# Audio-DAC-D.net
KiCad netlist of a schematic drawn in EAGLE
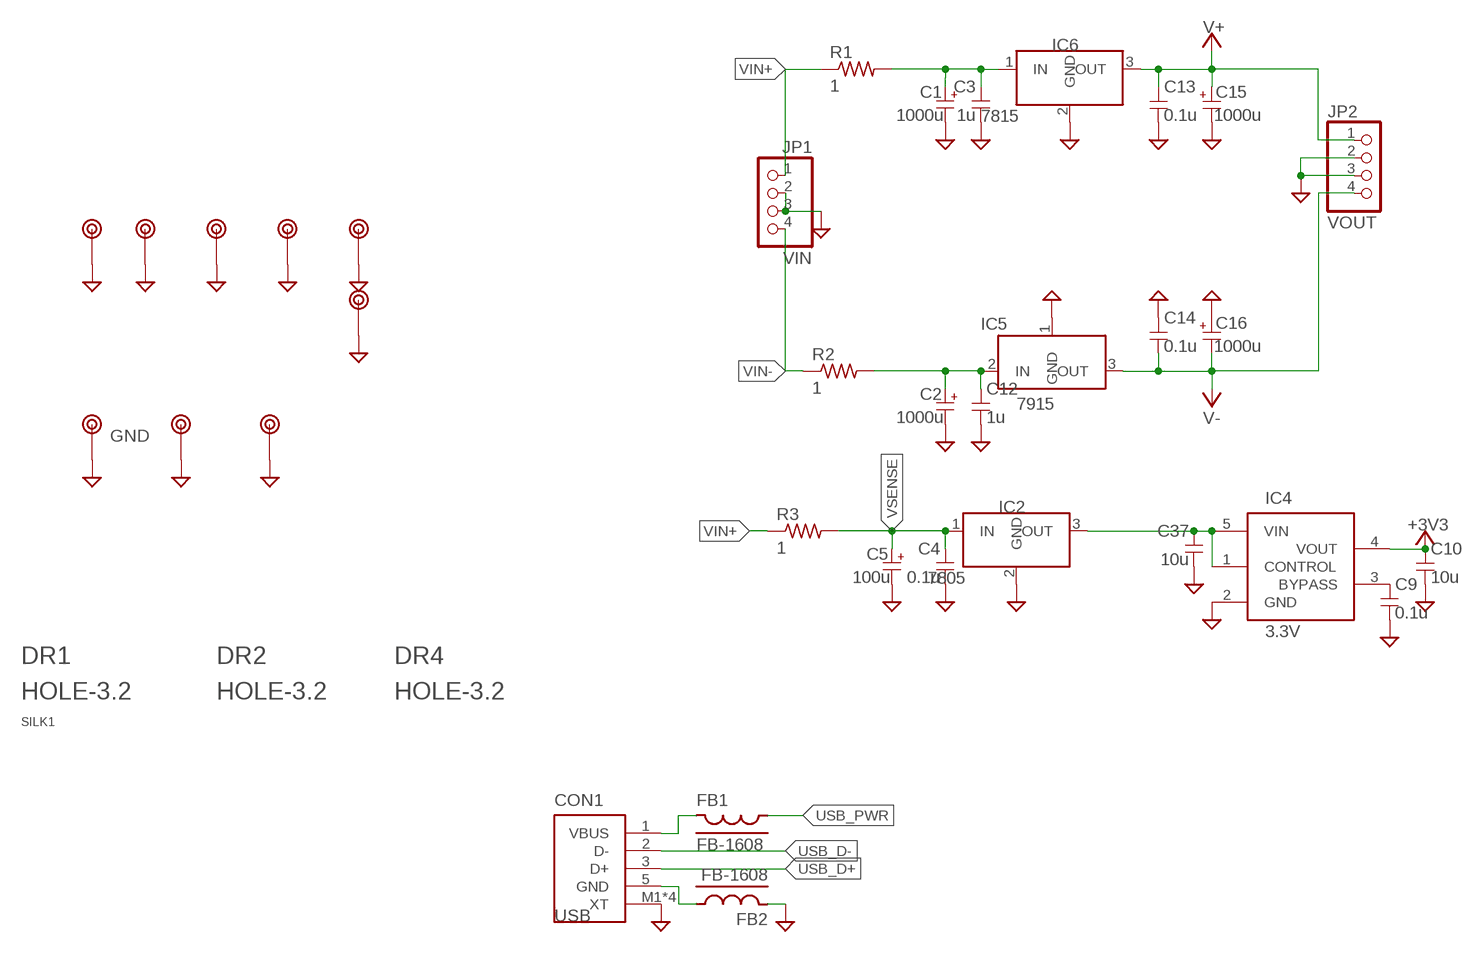
[diagram p0: schematic, sheet 1, part 1 of 2]
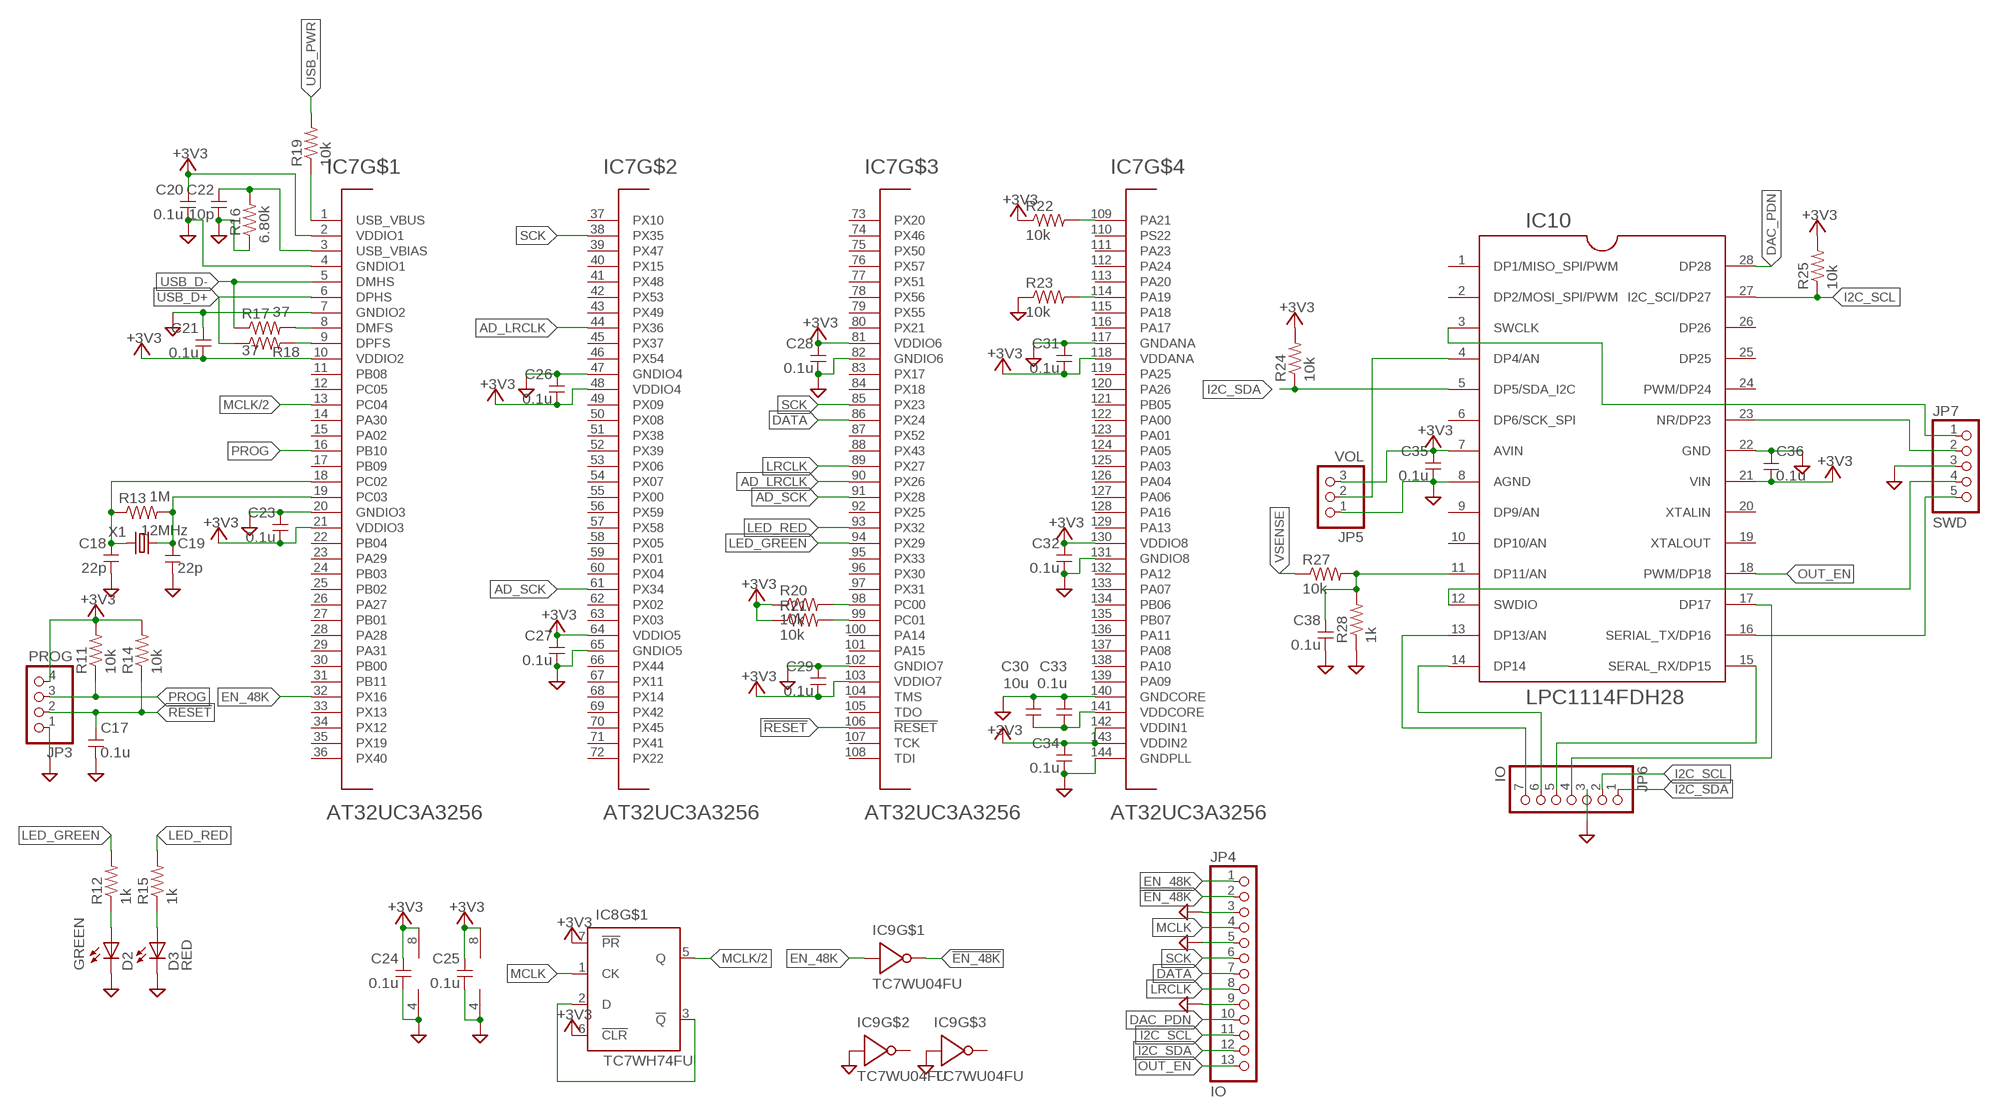
[diagram p1: schematic, sheet 1, part 2 of 2]

(export (version "E")
  (design (tool "Eeschema 10.0.6"))
  (components
    (comp (ref "C1")
      (value "1000u")
      (footprint "eagle-import:E5-10")
      (libsource (lib "eagle-import") (part "CPOLE5-10"))
    )
    (comp (ref "C2")
      (value "1000u")
      (footprint "eagle-import:E5-10")
      (libsource (lib "eagle-import") (part "CPOLE5-10"))
    )
    (comp (ref "C3")
      (value "1u")
      (footprint "eagle-import:1608")
      (libsource (lib "eagle-import") (part "C-1608"))
    )
    (comp (ref "C4")
      (value "0.1u")
      (footprint "eagle-import:1608")
      (libsource (lib "eagle-import") (part "C-1608"))
    )
    (comp (ref "C5")
      (value "100u")
      (footprint "eagle-import:E2.5-6.5")
      (libsource (lib "eagle-import") (part "CPOLE2.5-6.5"))
    )
    (comp (ref "C9")
      (value "0.1u")
      (footprint "eagle-import:1608")
      (libsource (lib "eagle-import") (part "C-1608"))
    )
    (comp (ref "C10")
      (value "10u")
      (footprint "eagle-import:2012")
      (libsource (lib "eagle-import") (part "C-2012"))
    )
    (comp (ref "C12")
      (value "1u")
      (footprint "eagle-import:1608")
      (libsource (lib "eagle-import") (part "C-1608"))
    )
    (comp (ref "C13")
      (value "0.1u")
      (footprint "eagle-import:2012")
      (libsource (lib "eagle-import") (part "C-2012"))
    )
    (comp (ref "C14")
      (value "0.1u")
      (footprint "eagle-import:2012")
      (libsource (lib "eagle-import") (part "C-2012"))
    )
    (comp (ref "C15")
      (value "1000u")
      (footprint "eagle-import:E5-10")
      (libsource (lib "eagle-import") (part "CPOLE5-10"))
    )
    (comp (ref "C16")
      (value "1000u")
      (footprint "eagle-import:E5-10")
      (libsource (lib "eagle-import") (part "CPOLE5-10"))
    )
    (comp (ref "C17")
      (value "0.1u")
      (footprint "eagle-import:1608")
      (libsource (lib "eagle-import") (part "C-1608"))
    )
    (comp (ref "C18")
      (value "22p")
      (footprint "eagle-import:1608")
      (libsource (lib "eagle-import") (part "C-1608"))
    )
    (comp (ref "C19")
      (value "22p")
      (footprint "eagle-import:1608")
      (libsource (lib "eagle-import") (part "C-1608"))
    )
    (comp (ref "C20")
      (value "0.1u")
      (footprint "eagle-import:1608")
      (libsource (lib "eagle-import") (part "C-1608"))
    )
    (comp (ref "C21")
      (value "0.1u")
      (footprint "eagle-import:1608")
      (libsource (lib "eagle-import") (part "C-1608"))
    )
    (comp (ref "C22")
      (value "10p")
      (footprint "eagle-import:1608")
      (libsource (lib "eagle-import") (part "C-1608"))
    )
    (comp (ref "C23")
      (value "0.1u")
      (footprint "eagle-import:1608")
      (libsource (lib "eagle-import") (part "C-1608"))
    )
    (comp (ref "C24")
      (value "0.1u")
      (footprint "eagle-import:1608")
      (libsource (lib "eagle-import") (part "C-1608"))
    )
    (comp (ref "C25")
      (value "0.1u")
      (footprint "eagle-import:1608")
      (libsource (lib "eagle-import") (part "C-1608"))
    )
    (comp (ref "C26")
      (value "0.1u")
      (footprint "eagle-import:1608")
      (libsource (lib "eagle-import") (part "C-1608"))
    )
    (comp (ref "C27")
      (value "0.1u")
      (footprint "eagle-import:1608")
      (libsource (lib "eagle-import") (part "C-1608"))
    )
    (comp (ref "C28")
      (value "0.1u")
      (footprint "eagle-import:1608")
      (libsource (lib "eagle-import") (part "C-1608"))
    )
    (comp (ref "C29")
      (value "0.1u")
      (footprint "eagle-import:1608")
      (libsource (lib "eagle-import") (part "C-1608"))
    )
    (comp (ref "C30")
      (value "10u")
      (footprint "eagle-import:2012")
      (libsource (lib "eagle-import") (part "C-2012"))
    )
    (comp (ref "C31")
      (value "0.1u")
      (footprint "eagle-import:1608")
      (libsource (lib "eagle-import") (part "C-1608"))
    )
    (comp (ref "C32")
      (value "0.1u")
      (footprint "eagle-import:1608")
      (libsource (lib "eagle-import") (part "C-1608"))
    )
    (comp (ref "C33")
      (value "0.1u")
      (footprint "eagle-import:1608")
      (libsource (lib "eagle-import") (part "C-1608"))
    )
    (comp (ref "C34")
      (value "0.1u")
      (footprint "eagle-import:1608")
      (libsource (lib "eagle-import") (part "C-1608"))
    )
    (comp (ref "C35")
      (value "0.1u")
      (footprint "eagle-import:1608")
      (libsource (lib "eagle-import") (part "C-1608"))
    )
    (comp (ref "C36")
      (value "0.1u")
      (footprint "eagle-import:1608")
      (libsource (lib "eagle-import") (part "C-1608"))
    )
    (comp (ref "C37")
      (value "10u")
      (footprint "eagle-import:2012")
      (libsource (lib "eagle-import") (part "C-2012"))
    )
    (comp (ref "C38")
      (value "0.1u")
      (footprint "eagle-import:1608")
      (libsource (lib "eagle-import") (part "C-1608"))
    )
    (comp (ref "CON1")
      (value "USB")
      (footprint "eagle-import:UX60A-MB-5ST")
      (libsource (lib "eagle-import") (part "USB"))
    )
    (comp (ref "D2")
      (value "GREEN")
      (footprint "eagle-import:D1608")
      (libsource (lib "eagle-import") (part "LED-SMD1608"))
    )
    (comp (ref "D3")
      (value "RED")
      (footprint "eagle-import:D1608")
      (libsource (lib "eagle-import") (part "LED-SMD1608"))
    )
    (comp (ref "DR1")
      (value "HOLE-3.2")
      (footprint "eagle-import:HOLE_3.2")
      (libsource (lib "eagle-import") (part "HOLE-3.2"))
    )
    (comp (ref "DR2")
      (value "HOLE-3.2")
      (footprint "eagle-import:HOLE_3.2")
      (libsource (lib "eagle-import") (part "HOLE-3.2"))
    )
    (comp (ref "DR4")
      (value "HOLE-3.2")
      (footprint "eagle-import:HOLE_3.2")
      (libsource (lib "eagle-import") (part "HOLE-3.2"))
    )
    (comp (ref "FB1")
      (value "FB-1608")
      (footprint "eagle-import:1608")
      (libsource (lib "eagle-import") (part "FB-1608"))
    )
    (comp (ref "FB2")
      (value "FB-1608")
      (footprint "eagle-import:1608")
      (libsource (lib "eagle-import") (part "FB-1608"))
    )
    (comp (ref "IC2")
      (value "7805")
      (footprint "eagle-import:7805-LARGEHOLE")
      (libsource (lib "eagle-import") (part "78X-1"))
    )
    (comp (ref "IC4")
      (value "3.3V")
      (footprint "eagle-import:SOT23-5")
      (libsource (lib "eagle-import") (part "NJM2863"))
    )
    (comp (ref "IC5")
      (value "7915")
      (footprint "eagle-import:7805-LARGEHOLE")
      (libsource (lib "eagle-import") (part "79X-1"))
    )
    (comp (ref "IC6")
      (value "7815")
      (footprint "eagle-import:7805-LARGEHOLE")
      (libsource (lib "eagle-import") (part "78X-1"))
    )
    (comp (ref "IC7")
      (value "AT32UC3A3256")
      (footprint "eagle-import:TQFP144")
      (libsource (lib "eagle-import") (part "AT32UC3A3256"))
    )
    (comp (ref "IC8")
      (value "TC7WH74FU")
      (footprint "eagle-import:SSOP8-P-0.65")
      (libsource (lib "eagle-import") (part "TC7WH74FU"))
    )
    (comp (ref "IC9")
      (value "TC7WU04FU")
      (footprint "eagle-import:SSOP8-P-0.65")
      (libsource (lib "eagle-import") (part "TC7WU04FU"))
    )
    (comp (ref "IC10")
      (value "LPC1114FDH28")
      (footprint "eagle-import:TSSOP28")
      (libsource (lib "eagle-import") (part "LPC1114FDH28"))
    )
    (comp (ref "JP1")
      (value "VIN")
      (footprint "eagle-import:1X04")
      (libsource (lib "eagle-import") (part "PINHD-1X4"))
    )
    (comp (ref "JP2")
      (value "VOUT")
      (footprint "eagle-import:1X04")
      (libsource (lib "eagle-import") (part "PINHD-1X4"))
    )
    (comp (ref "JP3")
      (value "PROG")
      (footprint "eagle-import:1X04")
      (libsource (lib "eagle-import") (part "PINHD-1X4"))
    )
    (comp (ref "JP4")
      (value "IO")
      (footprint "eagle-import:1X13")
      (libsource (lib "eagle-import") (part "PINHD-1X13"))
    )
    (comp (ref "JP5")
      (value "VOL")
      (footprint "eagle-import:1X03")
      (libsource (lib "eagle-import") (part "PINHD-1X3"))
    )
    (comp (ref "JP6")
      (value "IO")
      (footprint "eagle-import:1X07")
      (libsource (lib "eagle-import") (part "PINHD-1X7"))
    )
    (comp (ref "JP7")
      (value "SWD")
      (footprint "eagle-import:1X05")
      (libsource (lib "eagle-import") (part "PINHD-1X5"))
    )
    (comp (ref "R1")
      (value "1")
      (footprint "eagle-import:0204_7")
      (libsource (lib "eagle-import") (part "R-7.5"))
    )
    (comp (ref "R2")
      (value "1")
      (footprint "eagle-import:0204_7")
      (libsource (lib "eagle-import") (part "R-7.5"))
    )
    (comp (ref "R3")
      (value "1")
      (footprint "eagle-import:0204_7")
      (libsource (lib "eagle-import") (part "R-7.5"))
    )
    (comp (ref "R11")
      (value "10k")
      (footprint "eagle-import:1608")
      (libsource (lib "eagle-import") (part "R-1608"))
    )
    (comp (ref "R12")
      (value "1k")
      (footprint "eagle-import:1608")
      (libsource (lib "eagle-import") (part "R-1608"))
    )
    (comp (ref "R13")
      (value "1M")
      (footprint "eagle-import:0204_7")
      (libsource (lib "eagle-import") (part "R-7.5"))
    )
    (comp (ref "R14")
      (value "10k")
      (footprint "eagle-import:1608")
      (libsource (lib "eagle-import") (part "R-1608"))
    )
    (comp (ref "R15")
      (value "1k")
      (footprint "eagle-import:1608")
      (libsource (lib "eagle-import") (part "R-1608"))
    )
    (comp (ref "R16")
      (value "6.80k")
      (footprint "eagle-import:1608")
      (libsource (lib "eagle-import") (part "R-1608"))
    )
    (comp (ref "R17")
      (value "37")
      (footprint "eagle-import:1608")
      (libsource (lib "eagle-import") (part "R-1608"))
    )
    (comp (ref "R18")
      (value "37")
      (footprint "eagle-import:1608")
      (libsource (lib "eagle-import") (part "R-1608"))
    )
    (comp (ref "R19")
      (value "10k")
      (footprint "eagle-import:1608")
      (libsource (lib "eagle-import") (part "R-1608"))
    )
    (comp (ref "R20")
      (value "10k")
      (footprint "eagle-import:1608")
      (libsource (lib "eagle-import") (part "R-1608"))
    )
    (comp (ref "R21")
      (value "10k")
      (footprint "eagle-import:1608")
      (libsource (lib "eagle-import") (part "R-1608"))
    )
    (comp (ref "R22")
      (value "10k")
      (footprint "eagle-import:1608")
      (libsource (lib "eagle-import") (part "R-1608"))
    )
    (comp (ref "R23")
      (value "10k")
      (footprint "eagle-import:1608")
      (libsource (lib "eagle-import") (part "R-1608"))
    )
    (comp (ref "R24")
      (value "10k")
      (footprint "eagle-import:1608")
      (libsource (lib "eagle-import") (part "R-1608"))
    )
    (comp (ref "R25")
      (value "10k")
      (footprint "eagle-import:1608")
      (libsource (lib "eagle-import") (part "R-1608"))
    )
    (comp (ref "R27")
      (value "10k")
      (footprint "eagle-import:1608")
      (libsource (lib "eagle-import") (part "R-1608"))
    )
    (comp (ref "R28")
      (value "1k")
      (footprint "eagle-import:1608")
      (libsource (lib "eagle-import") (part "R-1608"))
    )
    (comp (ref "SILK1")
      (value "ROBOTECHWHEELSILK-9MM")
      (footprint "eagle-import:ROBOTECHWHEEL-9MM")
      (libsource (lib "eagle-import") (part "ROBOTECHWHEELSILK-9MM"))
    )
    (comp (ref "TP1")
      (value "TESTPIN")
      (footprint "eagle-import:TESTPIN")
      (libsource (lib "eagle-import") (part "TESTPIN"))
    )
    (comp (ref "TP2")
      (value "GND")
      (footprint "eagle-import:TESTPIN")
      (libsource (lib "eagle-import") (part "TESTPIN"))
    )
    (comp (ref "TP3")
      (value "TESTPIN")
      (footprint "eagle-import:TESTPIN")
      (libsource (lib "eagle-import") (part "TESTPIN"))
    )
    (comp (ref "TP4")
      (value "TESTPIN")
      (footprint "eagle-import:TESTPIN")
      (libsource (lib "eagle-import") (part "TESTPIN"))
    )
    (comp (ref "TP5")
      (value "TESTPIN")
      (footprint "eagle-import:TESTPIN")
      (libsource (lib "eagle-import") (part "TESTPIN"))
    )
    (comp (ref "TP6")
      (value "TESTPIN")
      (footprint "eagle-import:TESTPIN")
      (libsource (lib "eagle-import") (part "TESTPIN"))
    )
    (comp (ref "TP7")
      (value "TESTPIN")
      (footprint "eagle-import:TESTPIN")
      (libsource (lib "eagle-import") (part "TESTPIN"))
    )
    (comp (ref "TP8")
      (value "TESTPIN")
      (footprint "eagle-import:TESTPIN")
      (libsource (lib "eagle-import") (part "TESTPIN"))
    )
    (comp (ref "TP9")
      (value "TESTPIN")
      (footprint "eagle-import:TESTPIN")
      (libsource (lib "eagle-import") (part "TESTPIN"))
    )
    (comp (ref "X1")
      (value "12MHz")
      (footprint "eagle-import:HC49_S")
      (libsource (lib "eagle-import") (part "CRYSTALHC49S"))
    )
  )
  (nets
    (net (code "1") (name "+3V3") (class "Default")
      (node (ref "C10") (pin "1") (pinfunction "1_1") (pintype "passive"))
      (node (ref "C20") (pin "1") (pinfunction "1_1") (pintype "passive"))
      (node (ref "C21") (pin "2") (pinfunction "2_2") (pintype "passive"))
      (node (ref "C23") (pin "2") (pinfunction "2_2") (pintype "passive"))
      (node (ref "C24") (pin "1") (pinfunction "1_1") (pintype "passive"))
      (node (ref "C25") (pin "1") (pinfunction "1_1") (pintype "passive"))
      (node (ref "C26") (pin "2") (pinfunction "2_2") (pintype "passive"))
      (node (ref "C27") (pin "1") (pinfunction "1_1") (pintype "passive"))
      (node (ref "C28") (pin "1") (pinfunction "1_1") (pintype "passive"))
      (node (ref "C29") (pin "2") (pinfunction "2_2") (pintype "passive"))
      (node (ref "C31") (pin "2") (pinfunction "2_2") (pintype "passive"))
      (node (ref "C32") (pin "1") (pinfunction "1_1") (pintype "passive"))
      (node (ref "C34") (pin "1") (pinfunction "1_1") (pintype "passive"))
      (node (ref "C35") (pin "1") (pinfunction "1_1") (pintype "passive"))
      (node (ref "C36") (pin "2") (pinfunction "2_2") (pintype "passive"))
      (node (ref "IC10") (pin "21") (pinfunction "VIN_21") (pintype "power_in"))
      (node (ref "IC10") (pin "7") (pinfunction "AVIN_7") (pintype "power_in"))
      (node (ref "IC4") (pin "4") (pinfunction "VOUT_4") (pintype "power_in"))
      (node (ref "IC7") (pin "10") (pinfunction "VDDIO2_10") (pintype "power_in"))
      (node (ref "IC7") (pin "103") (pinfunction "VDDIO7_103") (pintype "power_in"))
      (node (ref "IC7") (pin "118") (pinfunction "VDDANA_118") (pintype "power_in"))
      (node (ref "IC7") (pin "130") (pinfunction "VDDIO8_130") (pintype "power_in"))
      (node (ref "IC7") (pin "142") (pinfunction "VDDIN1_142") (pintype "power_in"))
      (node (ref "IC7") (pin "143") (pinfunction "VDDIN2_143") (pintype "power_in"))
      (node (ref "IC7") (pin "2") (pinfunction "VDDIO1_2") (pintype "power_in"))
      (node (ref "IC7") (pin "21") (pinfunction "VDDIO3_21") (pintype "power_in"))
      (node (ref "IC7") (pin "48") (pinfunction "VDDIO4_48") (pintype "power_in"))
      (node (ref "IC7") (pin "64") (pinfunction "VDDIO5_64") (pintype "power_in"))
      (node (ref "IC7") (pin "81") (pinfunction "VDDIO6_81") (pintype "power_in"))
      (node (ref "IC8") (pin "6") (pinfunction "~{CLR}_6") (pintype "input"))
      (node (ref "IC8") (pin "7") (pinfunction "~{PR}_7") (pintype "input"))
      (node (ref "IC8") (pin "8") (pinfunction "V+_8") (pintype "power_in"))
      (node (ref "IC9") (pin "8") (pinfunction "V+_8") (pintype "power_in"))
      (node (ref "JP3") (pin "4") (pinfunction "4_4") (pintype "passive"))
      (node (ref "JP5") (pin "3") (pinfunction "3_3") (pintype "passive"))
      (node (ref "R11") (pin "2") (pinfunction "2_2") (pintype "passive"))
      (node (ref "R14") (pin "2") (pinfunction "2_2") (pintype "passive"))
      (node (ref "R20") (pin "1") (pinfunction "1_1") (pintype "passive"))
      (node (ref "R21") (pin "1") (pinfunction "1_1") (pintype "passive"))
      (node (ref "R22") (pin "1") (pinfunction "1_1") (pintype "passive"))
      (node (ref "R24") (pin "2") (pinfunction "2_2") (pintype "passive"))
      (node (ref "R25") (pin "2") (pinfunction "2_2") (pintype "passive"))
    )
    (net (code "2") (name "/~{EN_48K}") (class "Default")
      (node (ref "IC9") (pin "7") (pinfunction "P$2_7") (pintype "output"))
      (node (ref "JP4") (pin "2") (pinfunction "2_2") (pintype "passive"))
    )
    (net (code "3") (name "/~{RESET}") (class "Default")
      (node (ref "C17") (pin "1") (pinfunction "1_1") (pintype "passive"))
      (node (ref "IC7") (pin "106") (pinfunction "~{RESET}_106") (pintype "input"))
      (node (ref "JP3") (pin "2") (pinfunction "2_2") (pintype "passive"))
      (node (ref "R14") (pin "1") (pinfunction "1_1") (pintype "passive"))
    )
    (net (code "4") (name "AD_LRCLK") (class "Default")
      (node (ref "IC7") (pin "44") (pinfunction "PX36_44") (pintype "bidirectional"))
      (node (ref "IC7") (pin "90") (pinfunction "PX26_90") (pintype "bidirectional"))
    )
    (net (code "5") (name "AD_SCK") (class "Default")
      (node (ref "IC7") (pin "61") (pinfunction "PX34_61") (pintype "bidirectional"))
      (node (ref "IC7") (pin "91") (pinfunction "PX28_91") (pintype "bidirectional"))
    )
    (net (code "6") (name "DAC_PDN") (class "Default")
      (node (ref "IC10") (pin "28") (pinfunction "DP28_28") (pintype "bidirectional"))
      (node (ref "JP4") (pin "10") (pinfunction "10_10") (pintype "passive"))
    )
    (net (code "7") (name "DATA") (class "Default")
      (node (ref "IC7") (pin "86") (pinfunction "PX24_86") (pintype "bidirectional"))
      (node (ref "JP4") (pin "7") (pinfunction "7_7") (pintype "passive"))
    )
    (net (code "8") (name "EN_48K") (class "Default")
      (node (ref "IC7") (pin "32") (pinfunction "PX16_32") (pintype "bidirectional"))
      (node (ref "IC9") (pin "1") (pinfunction "P$1_1") (pintype "input"))
      (node (ref "JP4") (pin "1") (pinfunction "1_1") (pintype "passive"))
    )
    (net (code "9") (name "GND") (class "Default")
      (node (ref "C1") (pin "-") (pinfunction "2_-") (pintype "passive"))
      (node (ref "C10") (pin "2") (pinfunction "2_2") (pintype "passive"))
      (node (ref "C12") (pin "2") (pinfunction "2_2") (pintype "passive"))
      (node (ref "C13") (pin "2") (pinfunction "2_2") (pintype "passive"))
      (node (ref "C14") (pin "1") (pinfunction "1_1") (pintype "passive"))
      (node (ref "C15") (pin "-") (pinfunction "2_-") (pintype "passive"))
      (node (ref "C16") (pin "+") (pinfunction "1_+") (pintype "passive"))
      (node (ref "C17") (pin "2") (pinfunction "2_2") (pintype "passive"))
      (node (ref "C18") (pin "2") (pinfunction "2_2") (pintype "passive"))
      (node (ref "C19") (pin "2") (pinfunction "2_2") (pintype "passive"))
      (node (ref "C2") (pin "-") (pinfunction "2_-") (pintype "passive"))
      (node (ref "C20") (pin "2") (pinfunction "2_2") (pintype "passive"))
      (node (ref "C21") (pin "1") (pinfunction "1_1") (pintype "passive"))
      (node (ref "C22") (pin "2") (pinfunction "2_2") (pintype "passive"))
      (node (ref "C23") (pin "1") (pinfunction "1_1") (pintype "passive"))
      (node (ref "C24") (pin "2") (pinfunction "2_2") (pintype "passive"))
      (node (ref "C25") (pin "2") (pinfunction "2_2") (pintype "passive"))
      (node (ref "C26") (pin "1") (pinfunction "1_1") (pintype "passive"))
      (node (ref "C27") (pin "2") (pinfunction "2_2") (pintype "passive"))
      (node (ref "C28") (pin "2") (pinfunction "2_2") (pintype "passive"))
      (node (ref "C29") (pin "1") (pinfunction "1_1") (pintype "passive"))
      (node (ref "C3") (pin "2") (pinfunction "2_2") (pintype "passive"))
      (node (ref "C30") (pin "1") (pinfunction "1_1") (pintype "passive"))
      (node (ref "C31") (pin "1") (pinfunction "1_1") (pintype "passive"))
      (node (ref "C32") (pin "2") (pinfunction "2_2") (pintype "passive"))
      (node (ref "C33") (pin "1") (pinfunction "1_1") (pintype "passive"))
      (node (ref "C34") (pin "2") (pinfunction "2_2") (pintype "passive"))
      (node (ref "C35") (pin "2") (pinfunction "2_2") (pintype "passive"))
      (node (ref "C36") (pin "1") (pinfunction "1_1") (pintype "passive"))
      (node (ref "C37") (pin "2") (pinfunction "2_2") (pintype "passive"))
      (node (ref "C38") (pin "2") (pinfunction "2_2") (pintype "passive"))
      (node (ref "C4") (pin "2") (pinfunction "2_2") (pintype "passive"))
      (node (ref "C5") (pin "-") (pinfunction "2_-") (pintype "passive"))
      (node (ref "C9") (pin "2") (pinfunction "2_2") (pintype "passive"))
      (node (ref "CON1") (pin "M1") (pinfunction "XT_M1") (pintype "power_in"))
      (node (ref "CON1") (pin "M2") (pinfunction "XT_M2") (pintype "power_in"))
      (node (ref "CON1") (pin "M3") (pinfunction "XT_M3") (pintype "power_in"))
      (node (ref "CON1") (pin "M4") (pinfunction "XT_M4") (pintype "power_in"))
      (node (ref "D2") (pin "K") (pinfunction "K_K") (pintype "passive"))
      (node (ref "D3") (pin "K") (pinfunction "K_K") (pintype "passive"))
      (node (ref "FB2") (pin "2") (pinfunction "2_2") (pintype "passive"))
      (node (ref "IC10") (pin "22") (pinfunction "GND_22") (pintype "power_in"))
      (node (ref "IC10") (pin "8") (pinfunction "AGND_8") (pintype "power_in"))
      (node (ref "IC2") (pin "2") (pinfunction "GND_2") (pintype "power_in"))
      (node (ref "IC4") (pin "2") (pinfunction "GND_2") (pintype "power_in"))
      (node (ref "IC5") (pin "1") (pinfunction "GND_1") (pintype "input"))
      (node (ref "IC6") (pin "2") (pinfunction "GND_2") (pintype "power_in"))
      (node (ref "IC7") (pin "102") (pinfunction "GNDIO7_102") (pintype "power_in"))
      (node (ref "IC7") (pin "117") (pinfunction "GNDANA_117") (pintype "power_in"))
      (node (ref "IC7") (pin "131") (pinfunction "GNDIO8_131") (pintype "power_in"))
      (node (ref "IC7") (pin "140") (pinfunction "GNDCORE_140") (pintype "power_in"))
      (node (ref "IC7") (pin "144") (pinfunction "GNDPLL_144") (pintype "power_in"))
      (node (ref "IC7") (pin "20") (pinfunction "GNDIO3_20") (pintype "power_in"))
      (node (ref "IC7") (pin "4") (pinfunction "GNDIO1_4") (pintype "power_in"))
      (node (ref "IC7") (pin "47") (pinfunction "GNDIO4_47") (pintype "power_in"))
      (node (ref "IC7") (pin "65") (pinfunction "GNDIO5_65") (pintype "power_in"))
      (node (ref "IC7") (pin "7") (pinfunction "GNDIO2_7") (pintype "power_in"))
      (node (ref "IC7") (pin "82") (pinfunction "GNDIO6_82") (pintype "power_in"))
      (node (ref "IC8") (pin "4") (pinfunction "V-_4") (pintype "power_in"))
      (node (ref "IC9") (pin "3") (pinfunction "P$1_3") (pintype "input"))
      (node (ref "IC9") (pin "4") (pinfunction "V-_4") (pintype "power_in"))
      (node (ref "IC9") (pin "6") (pinfunction "P$1_6") (pintype "input"))
      (node (ref "JP1") (pin "2") (pinfunction "2_2") (pintype "passive"))
      (node (ref "JP1") (pin "3") (pinfunction "3_3") (pintype "passive"))
      (node (ref "JP2") (pin "2") (pinfunction "2_2") (pintype "passive"))
      (node (ref "JP2") (pin "3") (pinfunction "3_3") (pintype "passive"))
      (node (ref "JP3") (pin "1") (pinfunction "1_1") (pintype "passive"))
      (node (ref "JP4") (pin "3") (pinfunction "3_3") (pintype "passive"))
      (node (ref "JP4") (pin "5") (pinfunction "5_5") (pintype "passive"))
      (node (ref "JP4") (pin "9") (pinfunction "9_9") (pintype "passive"))
      (node (ref "JP5") (pin "1") (pinfunction "1_1") (pintype "passive"))
      (node (ref "JP6") (pin "3") (pinfunction "3_3") (pintype "passive"))
      (node (ref "JP7") (pin "3") (pinfunction "3_3") (pintype "passive"))
      (node (ref "R16") (pin "1") (pinfunction "1_1") (pintype "passive"))
      (node (ref "R23") (pin "1") (pinfunction "1_1") (pintype "passive"))
      (node (ref "R28") (pin "1") (pinfunction "1_1") (pintype "passive"))
      (node (ref "TP1") (pin "1") (pinfunction "1_1") (pintype "passive"))
      (node (ref "TP2") (pin "1") (pinfunction "1_1") (pintype "passive"))
      (node (ref "TP3") (pin "1") (pinfunction "1_1") (pintype "passive"))
      (node (ref "TP4") (pin "1") (pinfunction "1_1") (pintype "passive"))
      (node (ref "TP5") (pin "1") (pinfunction "1_1") (pintype "passive"))
      (node (ref "TP6") (pin "1") (pinfunction "1_1") (pintype "passive"))
      (node (ref "TP7") (pin "1") (pinfunction "1_1") (pintype "passive"))
      (node (ref "TP8") (pin "1") (pinfunction "1_1") (pintype "passive"))
      (node (ref "TP9") (pin "1") (pinfunction "1_1") (pintype "passive"))
    )
    (net (code "10") (name "I2C_SCL") (class "Default")
      (node (ref "IC10") (pin "27") (pinfunction "I2C_SCI/DP27_27") (pintype "bidirectional"))
      (node (ref "JP4") (pin "11") (pinfunction "11_11") (pintype "passive"))
      (node (ref "JP6") (pin "2") (pinfunction "2_2") (pintype "passive"))
      (node (ref "R25") (pin "1") (pinfunction "1_1") (pintype "passive"))
    )
    (net (code "11") (name "I2C_SDA") (class "Default")
      (node (ref "IC10") (pin "5") (pinfunction "DP5/SDA_I2C_5") (pintype "bidirectional"))
      (node (ref "JP4") (pin "12") (pinfunction "12_12") (pintype "passive"))
      (node (ref "JP6") (pin "1") (pinfunction "1_1") (pintype "passive"))
      (node (ref "R24") (pin "1") (pinfunction "1_1") (pintype "passive"))
    )
    (net (code "12") (name "LED_GREEN") (class "Default")
      (node (ref "IC7") (pin "94") (pinfunction "PX29_94") (pintype "bidirectional"))
      (node (ref "R12") (pin "2") (pinfunction "2_2") (pintype "passive"))
    )
    (net (code "13") (name "LED_RED") (class "Default")
      (node (ref "IC7") (pin "93") (pinfunction "PX32_93") (pintype "bidirectional"))
      (node (ref "R15") (pin "2") (pinfunction "2_2") (pintype "passive"))
    )
    (net (code "14") (name "LRCLK") (class "Default")
      (node (ref "IC7") (pin "89") (pinfunction "PX27_89") (pintype "bidirectional"))
      (node (ref "JP4") (pin "8") (pinfunction "8_8") (pintype "passive"))
    )
    (net (code "15") (name "MCLK") (class "Default")
      (node (ref "IC8") (pin "1") (pinfunction "CK_1") (pintype "input"))
      (node (ref "JP4") (pin "4") (pinfunction "4_4") (pintype "passive"))
    )
    (net (code "16") (name "MCLK{slash}2") (class "Default")
      (node (ref "IC7") (pin "13") (pinfunction "PC04_13") (pintype "bidirectional"))
      (node (ref "IC8") (pin "5") (pinfunction "Q_5") (pintype "output"))
    )
    (net (code "17") (name "Net-(C1-1)") (class "Default")
      (node (ref "C1") (pin "+") (pinfunction "1_+") (pintype "passive"))
      (node (ref "C3") (pin "1") (pinfunction "1_1") (pintype "passive"))
      (node (ref "IC6") (pin "1") (pinfunction "IN_1") (pintype "power_in"))
      (node (ref "R1") (pin "2") (pinfunction "2_2") (pintype "passive"))
    )
    (net (code "18") (name "Net-(C2-1)") (class "Default")
      (node (ref "C12") (pin "1") (pinfunction "1_1") (pintype "passive"))
      (node (ref "C2") (pin "+") (pinfunction "1_+") (pintype "passive"))
      (node (ref "IC5") (pin "2") (pinfunction "IN_2") (pintype "input"))
      (node (ref "R2") (pin "2") (pinfunction "2_2") (pintype "passive"))
    )
    (net (code "19") (name "Net-(CON1-GND)") (class "Default")
      (node (ref "CON1") (pin "5") (pinfunction "GND_5") (pintype "power_in"))
      (node (ref "FB2") (pin "1") (pinfunction "1_1") (pintype "passive"))
    )
    (net (code "20") (name "Net-(CON1-VBUS)") (class "Default")
      (node (ref "CON1") (pin "1") (pinfunction "VBUS_1") (pintype "power_in"))
      (node (ref "FB1") (pin "2") (pinfunction "2_2") (pintype "passive"))
    )
    (net (code "21") (name "Net-(D2-PadA)") (class "Default")
      (node (ref "D2") (pin "A") (pinfunction "A_A") (pintype "passive"))
      (node (ref "R12") (pin "1") (pinfunction "1_1") (pintype "passive"))
    )
    (net (code "22") (name "Net-(D3-PadA)") (class "Default")
      (node (ref "D3") (pin "A") (pinfunction "A_A") (pintype "passive"))
      (node (ref "R15") (pin "1") (pinfunction "1_1") (pintype "passive"))
    )
    (net (code "23") (name "Net-(IC2-OUT)") (class "Default")
      (node (ref "C37") (pin "1") (pinfunction "1_1") (pintype "passive"))
      (node (ref "IC2") (pin "3") (pinfunction "OUT_3") (pintype "output"))
      (node (ref "IC4") (pin "1") (pinfunction "CONTROL_1") (pintype "input"))
      (node (ref "IC4") (pin "5") (pinfunction "VIN_5") (pintype "power_in"))
    )
    (net (code "24") (name "Net-(IC4-BYPASS)") (class "Default")
      (node (ref "C9") (pin "1") (pinfunction "1_1") (pintype "passive"))
      (node (ref "IC4") (pin "3") (pinfunction "BYPASS_3") (pintype "passive"))
    )
    (net (code "25") (name "Net-(IC7A-DMFS)") (class "Default")
      (node (ref "IC7") (pin "8") (pinfunction "DMFS_8") (pintype "bidirectional"))
      (node (ref "R17") (pin "2") (pinfunction "2_2") (pintype "passive"))
    )
    (net (code "26") (name "Net-(IC7A-DPFS)") (class "Default")
      (node (ref "IC7") (pin "9") (pinfunction "DPFS_9") (pintype "bidirectional"))
      (node (ref "R18") (pin "2") (pinfunction "2_2") (pintype "passive"))
    )
    (net (code "27") (name "Net-(IC7A-PC02)") (class "Default")
      (node (ref "C18") (pin "1") (pinfunction "1_1") (pintype "passive"))
      (node (ref "IC7") (pin "18") (pinfunction "PC02_18") (pintype "bidirectional"))
      (node (ref "R13") (pin "1") (pinfunction "1_1") (pintype "passive"))
      (node (ref "X1") (pin "2") (pinfunction "2_2") (pintype "passive"))
    )
    (net (code "28") (name "Net-(IC7A-PC03)") (class "Default")
      (node (ref "C19") (pin "1") (pinfunction "1_1") (pintype "passive"))
      (node (ref "IC7") (pin "19") (pinfunction "PC03_19") (pintype "bidirectional"))
      (node (ref "R13") (pin "2") (pinfunction "2_2") (pintype "passive"))
      (node (ref "X1") (pin "1") (pinfunction "1_1") (pintype "passive"))
    )
    (net (code "29") (name "Net-(IC7A-USB_VBIAS)") (class "Default")
      (node (ref "C22") (pin "1") (pinfunction "1_1") (pintype "passive"))
      (node (ref "IC7") (pin "3") (pinfunction "USB_VBIAS_3") (pintype "input"))
      (node (ref "R16") (pin "2") (pinfunction "2_2") (pintype "passive"))
    )
    (net (code "30") (name "Net-(IC7A-USB_VBUS)") (class "Default")
      (node (ref "IC7") (pin "1") (pinfunction "USB_VBUS_1") (pintype "input"))
      (node (ref "R19") (pin "1") (pinfunction "1_1") (pintype "passive"))
    )
    (net (code "31") (name "Net-(IC7C-PC00)") (class "Default")
      (node (ref "IC7") (pin "98") (pinfunction "PC00_98") (pintype "bidirectional"))
      (node (ref "R20") (pin "2") (pinfunction "2_2") (pintype "passive"))
    )
    (net (code "32") (name "Net-(IC7C-PC01)") (class "Default")
      (node (ref "IC7") (pin "99") (pinfunction "PC01_99") (pintype "bidirectional"))
      (node (ref "R21") (pin "2") (pinfunction "2_2") (pintype "passive"))
    )
    (net (code "33") (name "Net-(IC7D-PA19)") (class "Default")
      (node (ref "IC7") (pin "114") (pinfunction "PA19_114") (pintype "bidirectional"))
      (node (ref "R23") (pin "2") (pinfunction "2_2") (pintype "passive"))
    )
    (net (code "34") (name "Net-(IC7D-PA21)") (class "Default")
      (node (ref "IC7") (pin "109") (pinfunction "PA21_109") (pintype "bidirectional"))
      (node (ref "R22") (pin "2") (pinfunction "2_2") (pintype "passive"))
    )
    (net (code "35") (name "Net-(IC7D-VDDCORE)") (class "Default")
      (node (ref "C30") (pin "2") (pinfunction "2_2") (pintype "passive"))
      (node (ref "C33") (pin "2") (pinfunction "2_2") (pintype "passive"))
      (node (ref "IC7") (pin "141") (pinfunction "VDDCORE_141") (pintype "power_in"))
    )
    (net (code "36") (name "Net-(IC8A-D)") (class "Default")
      (node (ref "IC8") (pin "2") (pinfunction "D_2") (pintype "input"))
      (node (ref "IC8") (pin "3") (pinfunction "~{Q}_3") (pintype "output"))
    )
    (net (code "37") (name "Net-(IC10-DP4{slash}AN)") (class "Default")
      (node (ref "IC10") (pin "4") (pinfunction "DP4/AN_4") (pintype "bidirectional"))
      (node (ref "JP5") (pin "2") (pinfunction "2_2") (pintype "passive"))
    )
    (net (code "38") (name "Net-(IC10-DP11{slash}AN)") (class "Default")
      (node (ref "C38") (pin "1") (pinfunction "1_1") (pintype "passive"))
      (node (ref "IC10") (pin "11") (pinfunction "DP11/AN_11") (pintype "bidirectional"))
      (node (ref "R27") (pin "2") (pinfunction "2_2") (pintype "passive"))
      (node (ref "R28") (pin "2") (pinfunction "2_2") (pintype "passive"))
    )
    (net (code "39") (name "Net-(IC10-DP13{slash}AN)") (class "Default")
      (node (ref "IC10") (pin "13") (pinfunction "DP13/AN_13") (pintype "bidirectional"))
      (node (ref "JP6") (pin "7") (pinfunction "7_7") (pintype "passive"))
    )
    (net (code "40") (name "Net-(IC10-DP14)") (class "Default")
      (node (ref "IC10") (pin "14") (pinfunction "DP14_14") (pintype "bidirectional"))
      (node (ref "JP6") (pin "6") (pinfunction "6_6") (pintype "passive"))
    )
    (net (code "41") (name "Net-(IC10-DP17)") (class "Default")
      (node (ref "IC10") (pin "17") (pinfunction "DP17_17") (pintype "bidirectional"))
      (node (ref "JP6") (pin "4") (pinfunction "4_4") (pintype "passive"))
    )
    (net (code "42") (name "Net-(IC10-NR{slash}DP23)") (class "Default")
      (node (ref "IC10") (pin "23") (pinfunction "NR/DP23_23") (pintype "bidirectional"))
      (node (ref "JP7") (pin "2") (pinfunction "2_2") (pintype "passive"))
    )
    (net (code "43") (name "Net-(IC10-SERAL_RX{slash}DP15)") (class "Default")
      (node (ref "IC10") (pin "15") (pinfunction "SERAL_RX/DP15_15") (pintype "bidirectional"))
      (node (ref "JP6") (pin "5") (pinfunction "5_5") (pintype "passive"))
    )
    (net (code "44") (name "Net-(IC10-SERIAL_TX{slash}DP16)") (class "Default")
      (node (ref "IC10") (pin "16") (pinfunction "SERIAL_TX/DP16_16") (pintype "bidirectional"))
      (node (ref "JP7") (pin "5") (pinfunction "5_5") (pintype "passive"))
    )
    (net (code "45") (name "Net-(IC10-SWCLK)") (class "Default")
      (node (ref "IC10") (pin "3") (pinfunction "SWCLK_3") (pintype "bidirectional"))
      (node (ref "JP7") (pin "1") (pinfunction "1_1") (pintype "passive"))
    )
    (net (code "46") (name "Net-(IC10-SWDIO)") (class "Default")
      (node (ref "IC10") (pin "12") (pinfunction "SWDIO_12") (pintype "bidirectional"))
      (node (ref "JP7") (pin "4") (pinfunction "4_4") (pintype "passive"))
    )
    (net (code "47") (name "OUT_EN") (class "Default")
      (node (ref "IC10") (pin "18") (pinfunction "PWM/DP18_18") (pintype "bidirectional"))
      (node (ref "JP4") (pin "13") (pinfunction "13_13") (pintype "passive"))
    )
    (net (code "48") (name "PROG") (class "Default")
      (node (ref "IC7") (pin "16") (pinfunction "PB10_16") (pintype "bidirectional"))
      (node (ref "JP3") (pin "3") (pinfunction "3_3") (pintype "passive"))
      (node (ref "R11") (pin "1") (pinfunction "1_1") (pintype "passive"))
    )
    (net (code "49") (name "SCK") (class "Default")
      (node (ref "IC7") (pin "38") (pinfunction "PX35_38") (pintype "bidirectional"))
      (node (ref "IC7") (pin "85") (pinfunction "PX23_85") (pintype "bidirectional"))
      (node (ref "JP4") (pin "6") (pinfunction "6_6") (pintype "passive"))
    )
    (net (code "50") (name "USB_D+") (class "Default")
      (node (ref "CON1") (pin "3") (pinfunction "D+_3") (pintype "bidirectional"))
      (node (ref "IC7") (pin "6") (pinfunction "DPHS_6") (pintype "bidirectional"))
      (node (ref "R18") (pin "1") (pinfunction "1_1") (pintype "passive"))
    )
    (net (code "51") (name "USB_D-") (class "Default")
      (node (ref "CON1") (pin "2") (pinfunction "D-_2") (pintype "bidirectional"))
      (node (ref "IC7") (pin "5") (pinfunction "DMHS_5") (pintype "bidirectional"))
      (node (ref "R17") (pin "1") (pinfunction "1_1") (pintype "passive"))
    )
    (net (code "52") (name "USB_PWR") (class "Default")
      (node (ref "FB1") (pin "1") (pinfunction "1_1") (pintype "passive"))
      (node (ref "R19") (pin "2") (pinfunction "2_2") (pintype "passive"))
    )
    (net (code "53") (name "V+") (class "Default")
      (node (ref "C13") (pin "1") (pinfunction "1_1") (pintype "passive"))
      (node (ref "C15") (pin "+") (pinfunction "1_+") (pintype "passive"))
      (node (ref "IC6") (pin "3") (pinfunction "OUT_3") (pintype "output"))
      (node (ref "JP2") (pin "1") (pinfunction "1_1") (pintype "passive"))
    )
    (net (code "54") (name "V-") (class "Default")
      (node (ref "C14") (pin "2") (pinfunction "2_2") (pintype "passive"))
      (node (ref "C16") (pin "-") (pinfunction "2_-") (pintype "passive"))
      (node (ref "IC5") (pin "3") (pinfunction "OUT_3") (pintype "output"))
      (node (ref "JP2") (pin "4") (pinfunction "4_4") (pintype "passive"))
    )
    (net (code "55") (name "VIN+") (class "Default")
      (node (ref "JP1") (pin "1") (pinfunction "1_1") (pintype "passive"))
      (node (ref "R1") (pin "1") (pinfunction "1_1") (pintype "passive"))
      (node (ref "R3") (pin "1") (pinfunction "1_1") (pintype "passive"))
    )
    (net (code "56") (name "VIN-") (class "Default")
      (node (ref "JP1") (pin "4") (pinfunction "4_4") (pintype "passive"))
      (node (ref "R2") (pin "1") (pinfunction "1_1") (pintype "passive"))
    )
    (net (code "57") (name "VSENSE") (class "Default")
      (node (ref "C4") (pin "1") (pinfunction "1_1") (pintype "passive"))
      (node (ref "C5") (pin "+") (pinfunction "1_+") (pintype "passive"))
      (node (ref "IC2") (pin "1") (pinfunction "IN_1") (pintype "power_in"))
      (node (ref "R27") (pin "1") (pinfunction "1_1") (pintype "passive"))
      (node (ref "R3") (pin "2") (pinfunction "2_2") (pintype "passive"))
    )
    (net (code "58") (name "unconnected-(IC7A-PA02-Pad15)") (class "Default")
      (node (ref "IC7") (pin "15") (pinfunction "PA02_15") (pintype "bidirectional"))
    )
    (net (code "59") (name "unconnected-(IC7A-PA27-Pad26)") (class "Default")
      (node (ref "IC7") (pin "26") (pinfunction "PA27_26") (pintype "bidirectional"))
    )
    (net (code "60") (name "unconnected-(IC7A-PA28-Pad28)") (class "Default")
      (node (ref "IC7") (pin "28") (pinfunction "PA28_28") (pintype "bidirectional"))
    )
    (net (code "61") (name "unconnected-(IC7A-PA29-Pad23)") (class "Default")
      (node (ref "IC7") (pin "23") (pinfunction "PA29_23") (pintype "bidirectional"))
    )
    (net (code "62") (name "unconnected-(IC7A-PA30-Pad14)") (class "Default")
      (node (ref "IC7") (pin "14") (pinfunction "PA30_14") (pintype "bidirectional"))
    )
    (net (code "63") (name "unconnected-(IC7A-PA31-Pad29)") (class "Default")
      (node (ref "IC7") (pin "29") (pinfunction "PA31_29") (pintype "bidirectional"))
    )
    (net (code "64") (name "unconnected-(IC7A-PB00-Pad30)") (class "Default")
      (node (ref "IC7") (pin "30") (pinfunction "PB00_30") (pintype "bidirectional"))
    )
    (net (code "65") (name "unconnected-(IC7A-PB01-Pad27)") (class "Default")
      (node (ref "IC7") (pin "27") (pinfunction "PB01_27") (pintype "bidirectional"))
    )
    (net (code "66") (name "unconnected-(IC7A-PB02-Pad25)") (class "Default")
      (node (ref "IC7") (pin "25") (pinfunction "PB02_25") (pintype "bidirectional"))
    )
    (net (code "67") (name "unconnected-(IC7A-PB03-Pad24)") (class "Default")
      (node (ref "IC7") (pin "24") (pinfunction "PB03_24") (pintype "bidirectional"))
    )
    (net (code "68") (name "unconnected-(IC7A-PB04-Pad22)") (class "Default")
      (node (ref "IC7") (pin "22") (pinfunction "PB04_22") (pintype "bidirectional"))
    )
    (net (code "69") (name "unconnected-(IC7A-PB08-Pad11)") (class "Default")
      (node (ref "IC7") (pin "11") (pinfunction "PB08_11") (pintype "bidirectional"))
    )
    (net (code "70") (name "unconnected-(IC7A-PB09-Pad17)") (class "Default")
      (node (ref "IC7") (pin "17") (pinfunction "PB09_17") (pintype "bidirectional"))
    )
    (net (code "71") (name "unconnected-(IC7A-PB11-Pad31)") (class "Default")
      (node (ref "IC7") (pin "31") (pinfunction "PB11_31") (pintype "bidirectional"))
    )
    (net (code "72") (name "unconnected-(IC7A-PC05-Pad12)") (class "Default")
      (node (ref "IC7") (pin "12") (pinfunction "PC05_12") (pintype "bidirectional"))
    )
    (net (code "73") (name "unconnected-(IC7A-PX12-Pad34)") (class "Default")
      (node (ref "IC7") (pin "34") (pinfunction "PX12_34") (pintype "bidirectional"))
    )
    (net (code "74") (name "unconnected-(IC7A-PX13-Pad33)") (class "Default")
      (node (ref "IC7") (pin "33") (pinfunction "PX13_33") (pintype "bidirectional"))
    )
    (net (code "75") (name "unconnected-(IC7A-PX19-Pad35)") (class "Default")
      (node (ref "IC7") (pin "35") (pinfunction "PX19_35") (pintype "bidirectional"))
    )
    (net (code "76") (name "unconnected-(IC7A-PX40-Pad36)") (class "Default")
      (node (ref "IC7") (pin "36") (pinfunction "PX40_36") (pintype "bidirectional"))
    )
    (net (code "77") (name "unconnected-(IC7B-PX00-Pad55)") (class "Default")
      (node (ref "IC7") (pin "55") (pinfunction "PX00_55") (pintype "bidirectional"))
    )
    (net (code "78") (name "unconnected-(IC7B-PX01-Pad59)") (class "Default")
      (node (ref "IC7") (pin "59") (pinfunction "PX01_59") (pintype "bidirectional"))
    )
    (net (code "79") (name "unconnected-(IC7B-PX02-Pad62)") (class "Default")
      (node (ref "IC7") (pin "62") (pinfunction "PX02_62") (pintype "bidirectional"))
    )
    (net (code "80") (name "unconnected-(IC7B-PX03-Pad63)") (class "Default")
      (node (ref "IC7") (pin "63") (pinfunction "PX03_63") (pintype "bidirectional"))
    )
    (net (code "81") (name "unconnected-(IC7B-PX04-Pad60)") (class "Default")
      (node (ref "IC7") (pin "60") (pinfunction "PX04_60") (pintype "bidirectional"))
    )
    (net (code "82") (name "unconnected-(IC7B-PX05-Pad58)") (class "Default")
      (node (ref "IC7") (pin "58") (pinfunction "PX05_58") (pintype "bidirectional"))
    )
    (net (code "83") (name "unconnected-(IC7B-PX06-Pad53)") (class "Default")
      (node (ref "IC7") (pin "53") (pinfunction "PX06_53") (pintype "bidirectional"))
    )
    (net (code "84") (name "unconnected-(IC7B-PX07-Pad54)") (class "Default")
      (node (ref "IC7") (pin "54") (pinfunction "PX07_54") (pintype "bidirectional"))
    )
    (net (code "85") (name "unconnected-(IC7B-PX08-Pad50)") (class "Default")
      (node (ref "IC7") (pin "50") (pinfunction "PX08_50") (pintype "bidirectional"))
    )
    (net (code "86") (name "unconnected-(IC7B-PX09-Pad49)") (class "Default")
      (node (ref "IC7") (pin "49") (pinfunction "PX09_49") (pintype "bidirectional"))
    )
    (net (code "87") (name "unconnected-(IC7B-PX10-Pad37)") (class "Default")
      (node (ref "IC7") (pin "37") (pinfunction "PX10_37") (pintype "bidirectional"))
    )
    (net (code "88") (name "unconnected-(IC7B-PX11-Pad67)") (class "Default")
      (node (ref "IC7") (pin "67") (pinfunction "PX11_67") (pintype "bidirectional"))
    )
    (net (code "89") (name "unconnected-(IC7B-PX14-Pad68)") (class "Default")
      (node (ref "IC7") (pin "68") (pinfunction "PX14_68") (pintype "bidirectional"))
    )
    (net (code "90") (name "unconnected-(IC7B-PX15-Pad40)") (class "Default")
      (node (ref "IC7") (pin "40") (pinfunction "PX15_40") (pintype "bidirectional"))
    )
    (net (code "91") (name "unconnected-(IC7B-PX22-Pad72)") (class "Default")
      (node (ref "IC7") (pin "72") (pinfunction "PX22_72") (pintype "bidirectional"))
    )
    (net (code "92") (name "unconnected-(IC7B-PX37-Pad45)") (class "Default")
      (node (ref "IC7") (pin "45") (pinfunction "PX37_45") (pintype "bidirectional"))
    )
    (net (code "93") (name "unconnected-(IC7B-PX38-Pad51)") (class "Default")
      (node (ref "IC7") (pin "51") (pinfunction "PX38_51") (pintype "bidirectional"))
    )
    (net (code "94") (name "unconnected-(IC7B-PX39-Pad52)") (class "Default")
      (node (ref "IC7") (pin "52") (pinfunction "PX39_52") (pintype "bidirectional"))
    )
    (net (code "95") (name "unconnected-(IC7B-PX41-Pad71)") (class "Default")
      (node (ref "IC7") (pin "71") (pinfunction "PX41_71") (pintype "bidirectional"))
    )
    (net (code "96") (name "unconnected-(IC7B-PX42-Pad69)") (class "Default")
      (node (ref "IC7") (pin "69") (pinfunction "PX42_69") (pintype "bidirectional"))
    )
    (net (code "97") (name "unconnected-(IC7B-PX44-Pad66)") (class "Default")
      (node (ref "IC7") (pin "66") (pinfunction "PX44_66") (pintype "bidirectional"))
    )
    (net (code "98") (name "unconnected-(IC7B-PX45-Pad70)") (class "Default")
      (node (ref "IC7") (pin "70") (pinfunction "PX45_70") (pintype "bidirectional"))
    )
    (net (code "99") (name "unconnected-(IC7B-PX47-Pad39)") (class "Default")
      (node (ref "IC7") (pin "39") (pinfunction "PX47_39") (pintype "bidirectional"))
    )
    (net (code "100") (name "unconnected-(IC7B-PX48-Pad41)") (class "Default")
      (node (ref "IC7") (pin "41") (pinfunction "PX48_41") (pintype "bidirectional"))
    )
    (net (code "101") (name "unconnected-(IC7B-PX49-Pad43)") (class "Default")
      (node (ref "IC7") (pin "43") (pinfunction "PX49_43") (pintype "bidirectional"))
    )
    (net (code "102") (name "unconnected-(IC7B-PX53-Pad42)") (class "Default")
      (node (ref "IC7") (pin "42") (pinfunction "PX53_42") (pintype "bidirectional"))
    )
    (net (code "103") (name "unconnected-(IC7B-PX54-Pad46)") (class "Default")
      (node (ref "IC7") (pin "46") (pinfunction "PX54_46") (pintype "bidirectional"))
    )
    (net (code "104") (name "unconnected-(IC7B-PX58-Pad57)") (class "Default")
      (node (ref "IC7") (pin "57") (pinfunction "PX58_57") (pintype "bidirectional"))
    )
    (net (code "105") (name "unconnected-(IC7B-PX59-Pad56)") (class "Default")
      (node (ref "IC7") (pin "56") (pinfunction "PX59_56") (pintype "bidirectional"))
    )
    (net (code "106") (name "unconnected-(IC7C-PA14-Pad100)") (class "Default")
      (node (ref "IC7") (pin "100") (pinfunction "PA14_100") (pintype "bidirectional"))
    )
    (net (code "107") (name "unconnected-(IC7C-PA15-Pad101)") (class "Default")
      (node (ref "IC7") (pin "101") (pinfunction "PA15_101") (pintype "bidirectional"))
    )
    (net (code "108") (name "unconnected-(IC7C-PX17-Pad83)") (class "Default")
      (node (ref "IC7") (pin "83") (pinfunction "PX17_83") (pintype "bidirectional"))
    )
    (net (code "109") (name "unconnected-(IC7C-PX18-Pad84)") (class "Default")
      (node (ref "IC7") (pin "84") (pinfunction "PX18_84") (pintype "bidirectional"))
    )
    (net (code "110") (name "unconnected-(IC7C-PX20-Pad73)") (class "Default")
      (node (ref "IC7") (pin "73") (pinfunction "PX20_73") (pintype "bidirectional"))
    )
    (net (code "111") (name "unconnected-(IC7C-PX21-Pad80)") (class "Default")
      (node (ref "IC7") (pin "80") (pinfunction "PX21_80") (pintype "bidirectional"))
    )
    (net (code "112") (name "unconnected-(IC7C-PX25-Pad92)") (class "Default")
      (node (ref "IC7") (pin "92") (pinfunction "PX25_92") (pintype "bidirectional"))
    )
    (net (code "113") (name "unconnected-(IC7C-PX30-Pad96)") (class "Default")
      (node (ref "IC7") (pin "96") (pinfunction "PX30_96") (pintype "bidirectional"))
    )
    (net (code "114") (name "unconnected-(IC7C-PX31-Pad97)") (class "Default")
      (node (ref "IC7") (pin "97") (pinfunction "PX31_97") (pintype "bidirectional"))
    )
    (net (code "115") (name "unconnected-(IC7C-PX33-Pad95)") (class "Default")
      (node (ref "IC7") (pin "95") (pinfunction "PX33_95") (pintype "bidirectional"))
    )
    (net (code "116") (name "unconnected-(IC7C-PX43-Pad88)") (class "Default")
      (node (ref "IC7") (pin "88") (pinfunction "PX43_88") (pintype "bidirectional"))
    )
    (net (code "117") (name "unconnected-(IC7C-PX46-Pad74)") (class "Default")
      (node (ref "IC7") (pin "74") (pinfunction "PX46_74") (pintype "bidirectional"))
    )
    (net (code "118") (name "unconnected-(IC7C-PX50-Pad75)") (class "Default")
      (node (ref "IC7") (pin "75") (pinfunction "PX50_75") (pintype "bidirectional"))
    )
    (net (code "119") (name "unconnected-(IC7C-PX51-Pad77)") (class "Default")
      (node (ref "IC7") (pin "77") (pinfunction "PX51_77") (pintype "bidirectional"))
    )
    (net (code "120") (name "unconnected-(IC7C-PX52-Pad87)") (class "Default")
      (node (ref "IC7") (pin "87") (pinfunction "PX52_87") (pintype "bidirectional"))
    )
    (net (code "121") (name "unconnected-(IC7C-PX55-Pad79)") (class "Default")
      (node (ref "IC7") (pin "79") (pinfunction "PX55_79") (pintype "bidirectional"))
    )
    (net (code "122") (name "unconnected-(IC7C-PX56-Pad78)") (class "Default")
      (node (ref "IC7") (pin "78") (pinfunction "PX56_78") (pintype "bidirectional"))
    )
    (net (code "123") (name "unconnected-(IC7C-PX57-Pad76)") (class "Default")
      (node (ref "IC7") (pin "76") (pinfunction "PX57_76") (pintype "bidirectional"))
    )
    (net (code "124") (name "unconnected-(IC7C-TCK-Pad107)") (class "Default")
      (node (ref "IC7") (pin "107") (pinfunction "TCK_107") (pintype "bidirectional"))
    )
    (net (code "125") (name "unconnected-(IC7C-TDI-Pad108)") (class "Default")
      (node (ref "IC7") (pin "108") (pinfunction "TDI_108") (pintype "bidirectional"))
    )
    (net (code "126") (name "unconnected-(IC7C-TDO-Pad105)") (class "Default")
      (node (ref "IC7") (pin "105") (pinfunction "TDO_105") (pintype "bidirectional"))
    )
    (net (code "127") (name "unconnected-(IC7C-TMS-Pad104)") (class "Default")
      (node (ref "IC7") (pin "104") (pinfunction "TMS_104") (pintype "bidirectional"))
    )
    (net (code "128") (name "unconnected-(IC7D-PA00-Pad122)") (class "Default")
      (node (ref "IC7") (pin "122") (pinfunction "PA00_122") (pintype "bidirectional"))
    )
    (net (code "129") (name "unconnected-(IC7D-PA01-Pad123)") (class "Default")
      (node (ref "IC7") (pin "123") (pinfunction "PA01_123") (pintype "bidirectional"))
    )
    (net (code "130") (name "unconnected-(IC7D-PA03-Pad125)") (class "Default")
      (node (ref "IC7") (pin "125") (pinfunction "PA03_125") (pintype "bidirectional"))
    )
    (net (code "131") (name "unconnected-(IC7D-PA04-Pad126)") (class "Default")
      (node (ref "IC7") (pin "126") (pinfunction "PA04_126") (pintype "bidirectional"))
    )
    (net (code "132") (name "unconnected-(IC7D-PA05-Pad124)") (class "Default")
      (node (ref "IC7") (pin "124") (pinfunction "PA05_124") (pintype "bidirectional"))
    )
    (net (code "133") (name "unconnected-(IC7D-PA06-Pad127)") (class "Default")
      (node (ref "IC7") (pin "127") (pinfunction "PA06_127") (pintype "bidirectional"))
    )
    (net (code "134") (name "unconnected-(IC7D-PA07-Pad133)") (class "Default")
      (node (ref "IC7") (pin "133") (pinfunction "PA07_133") (pintype "bidirectional"))
    )
    (net (code "135") (name "unconnected-(IC7D-PA08-Pad137)") (class "Default")
      (node (ref "IC7") (pin "137") (pinfunction "PA08_137") (pintype "bidirectional"))
    )
    (net (code "136") (name "unconnected-(IC7D-PA09-Pad139)") (class "Default")
      (node (ref "IC7") (pin "139") (pinfunction "PA09_139") (pintype "bidirectional"))
    )
    (net (code "137") (name "unconnected-(IC7D-PA10-Pad138)") (class "Default")
      (node (ref "IC7") (pin "138") (pinfunction "PA10_138") (pintype "bidirectional"))
    )
    (net (code "138") (name "unconnected-(IC7D-PA11-Pad136)") (class "Default")
      (node (ref "IC7") (pin "136") (pinfunction "PA11_136") (pintype "bidirectional"))
    )
    (net (code "139") (name "unconnected-(IC7D-PA12-Pad132)") (class "Default")
      (node (ref "IC7") (pin "132") (pinfunction "PA12_132") (pintype "bidirectional"))
    )
    (net (code "140") (name "unconnected-(IC7D-PA13-Pad129)") (class "Default")
      (node (ref "IC7") (pin "129") (pinfunction "PA13_129") (pintype "bidirectional"))
    )
    (net (code "141") (name "unconnected-(IC7D-PA16-Pad128)") (class "Default")
      (node (ref "IC7") (pin "128") (pinfunction "PA16_128") (pintype "bidirectional"))
    )
    (net (code "142") (name "unconnected-(IC7D-PA17-Pad116)") (class "Default")
      (node (ref "IC7") (pin "116") (pinfunction "PA17_116") (pintype "bidirectional"))
    )
    (net (code "143") (name "unconnected-(IC7D-PA18-Pad115)") (class "Default")
      (node (ref "IC7") (pin "115") (pinfunction "PA18_115") (pintype "bidirectional"))
    )
    (net (code "144") (name "unconnected-(IC7D-PA20-Pad113)") (class "Default")
      (node (ref "IC7") (pin "113") (pinfunction "PA20_113") (pintype "bidirectional"))
    )
    (net (code "145") (name "unconnected-(IC7D-PA23-Pad111)") (class "Default")
      (node (ref "IC7") (pin "111") (pinfunction "PA23_111") (pintype "bidirectional"))
    )
    (net (code "146") (name "unconnected-(IC7D-PA24-Pad112)") (class "Default")
      (node (ref "IC7") (pin "112") (pinfunction "PA24_112") (pintype "bidirectional"))
    )
    (net (code "147") (name "unconnected-(IC7D-PA25-Pad119)") (class "Default")
      (node (ref "IC7") (pin "119") (pinfunction "PA25_119") (pintype "bidirectional"))
    )
    (net (code "148") (name "unconnected-(IC7D-PA26-Pad120)") (class "Default")
      (node (ref "IC7") (pin "120") (pinfunction "PA26_120") (pintype "bidirectional"))
    )
    (net (code "149") (name "unconnected-(IC7D-PB05-Pad121)") (class "Default")
      (node (ref "IC7") (pin "121") (pinfunction "PB05_121") (pintype "bidirectional"))
    )
    (net (code "150") (name "unconnected-(IC7D-PB06-Pad134)") (class "Default")
      (node (ref "IC7") (pin "134") (pinfunction "PB06_134") (pintype "bidirectional"))
    )
    (net (code "151") (name "unconnected-(IC7D-PB07-Pad135)") (class "Default")
      (node (ref "IC7") (pin "135") (pinfunction "PB07_135") (pintype "bidirectional"))
    )
    (net (code "152") (name "unconnected-(IC7D-PS22-Pad110)") (class "Default")
      (node (ref "IC7") (pin "110") (pinfunction "PS22_110") (pintype "bidirectional"))
    )
    (net (code "153") (name "unconnected-(IC9B-P$2-Pad2)") (class "Default")
      (node (ref "IC9") (pin "2") (pinfunction "P$2_2") (pintype "output"))
    )
    (net (code "154") (name "unconnected-(IC9C-P$2-Pad5)") (class "Default")
      (node (ref "IC9") (pin "5") (pinfunction "P$2_5") (pintype "output"))
    )
    (net (code "155") (name "unconnected-(IC10-DP1{slash}MISO_SPI{slash}PWM-Pad1)") (class "Default")
      (node (ref "IC10") (pin "1") (pinfunction "DP1/MISO_SPI/PWM_1") (pintype "bidirectional"))
    )
    (net (code "156") (name "unconnected-(IC10-DP2{slash}MOSI_SPI{slash}PWM-Pad2)") (class "Default")
      (node (ref "IC10") (pin "2") (pinfunction "DP2/MOSI_SPI/PWM_2") (pintype "bidirectional"))
    )
    (net (code "157") (name "unconnected-(IC10-DP6{slash}SCK_SPI-Pad6)") (class "Default")
      (node (ref "IC10") (pin "6") (pinfunction "DP6/SCK_SPI_6") (pintype "bidirectional"))
    )
    (net (code "158") (name "unconnected-(IC10-DP9{slash}AN-Pad9)") (class "Default")
      (node (ref "IC10") (pin "9") (pinfunction "DP9/AN_9") (pintype "bidirectional"))
    )
    (net (code "159") (name "unconnected-(IC10-DP10{slash}AN-Pad10)") (class "Default")
      (node (ref "IC10") (pin "10") (pinfunction "DP10/AN_10") (pintype "bidirectional"))
    )
    (net (code "160") (name "unconnected-(IC10-DP25-Pad25)") (class "Default")
      (node (ref "IC10") (pin "25") (pinfunction "DP25_25") (pintype "bidirectional"))
    )
    (net (code "161") (name "unconnected-(IC10-DP26-Pad26)") (class "Default")
      (node (ref "IC10") (pin "26") (pinfunction "DP26_26") (pintype "bidirectional"))
    )
    (net (code "162") (name "unconnected-(IC10-PWM{slash}DP24-Pad24)") (class "Default")
      (node (ref "IC10") (pin "24") (pinfunction "PWM/DP24_24") (pintype "bidirectional"))
    )
    (net (code "163") (name "unconnected-(IC10-XTALIN-Pad20)") (class "Default")
      (node (ref "IC10") (pin "20") (pinfunction "XTALIN_20") (pintype "passive"))
    )
    (net (code "164") (name "unconnected-(IC10-XTALOUT-Pad19)") (class "Default")
      (node (ref "IC10") (pin "19") (pinfunction "XTALOUT_19") (pintype "passive"))
    )
  )
)
